# PB_LAN9500.net
KiCad netlist of a schematic drawn in EAGLE
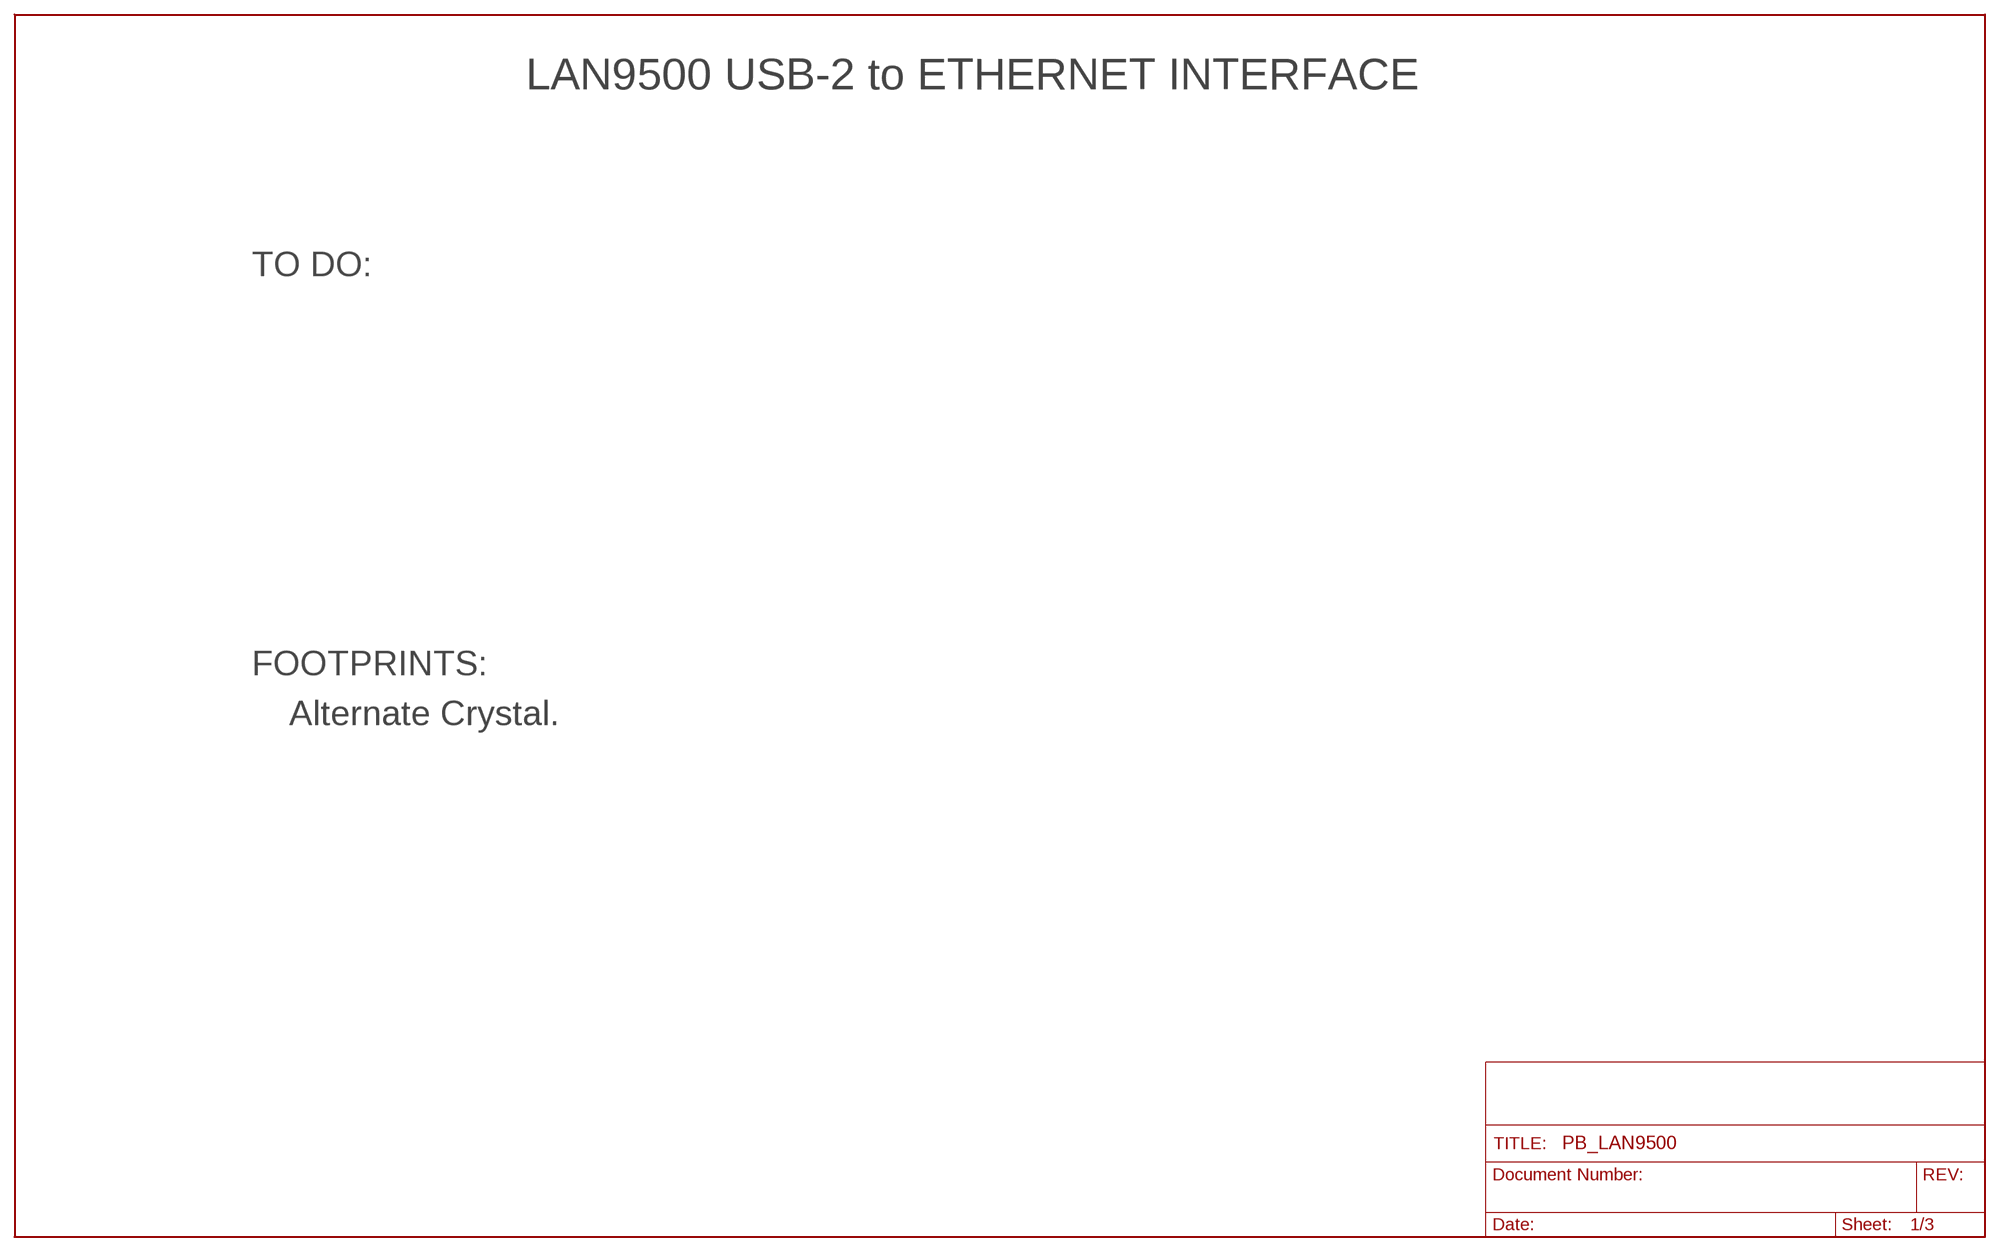
[diagram p0: schematic, sheet 1]
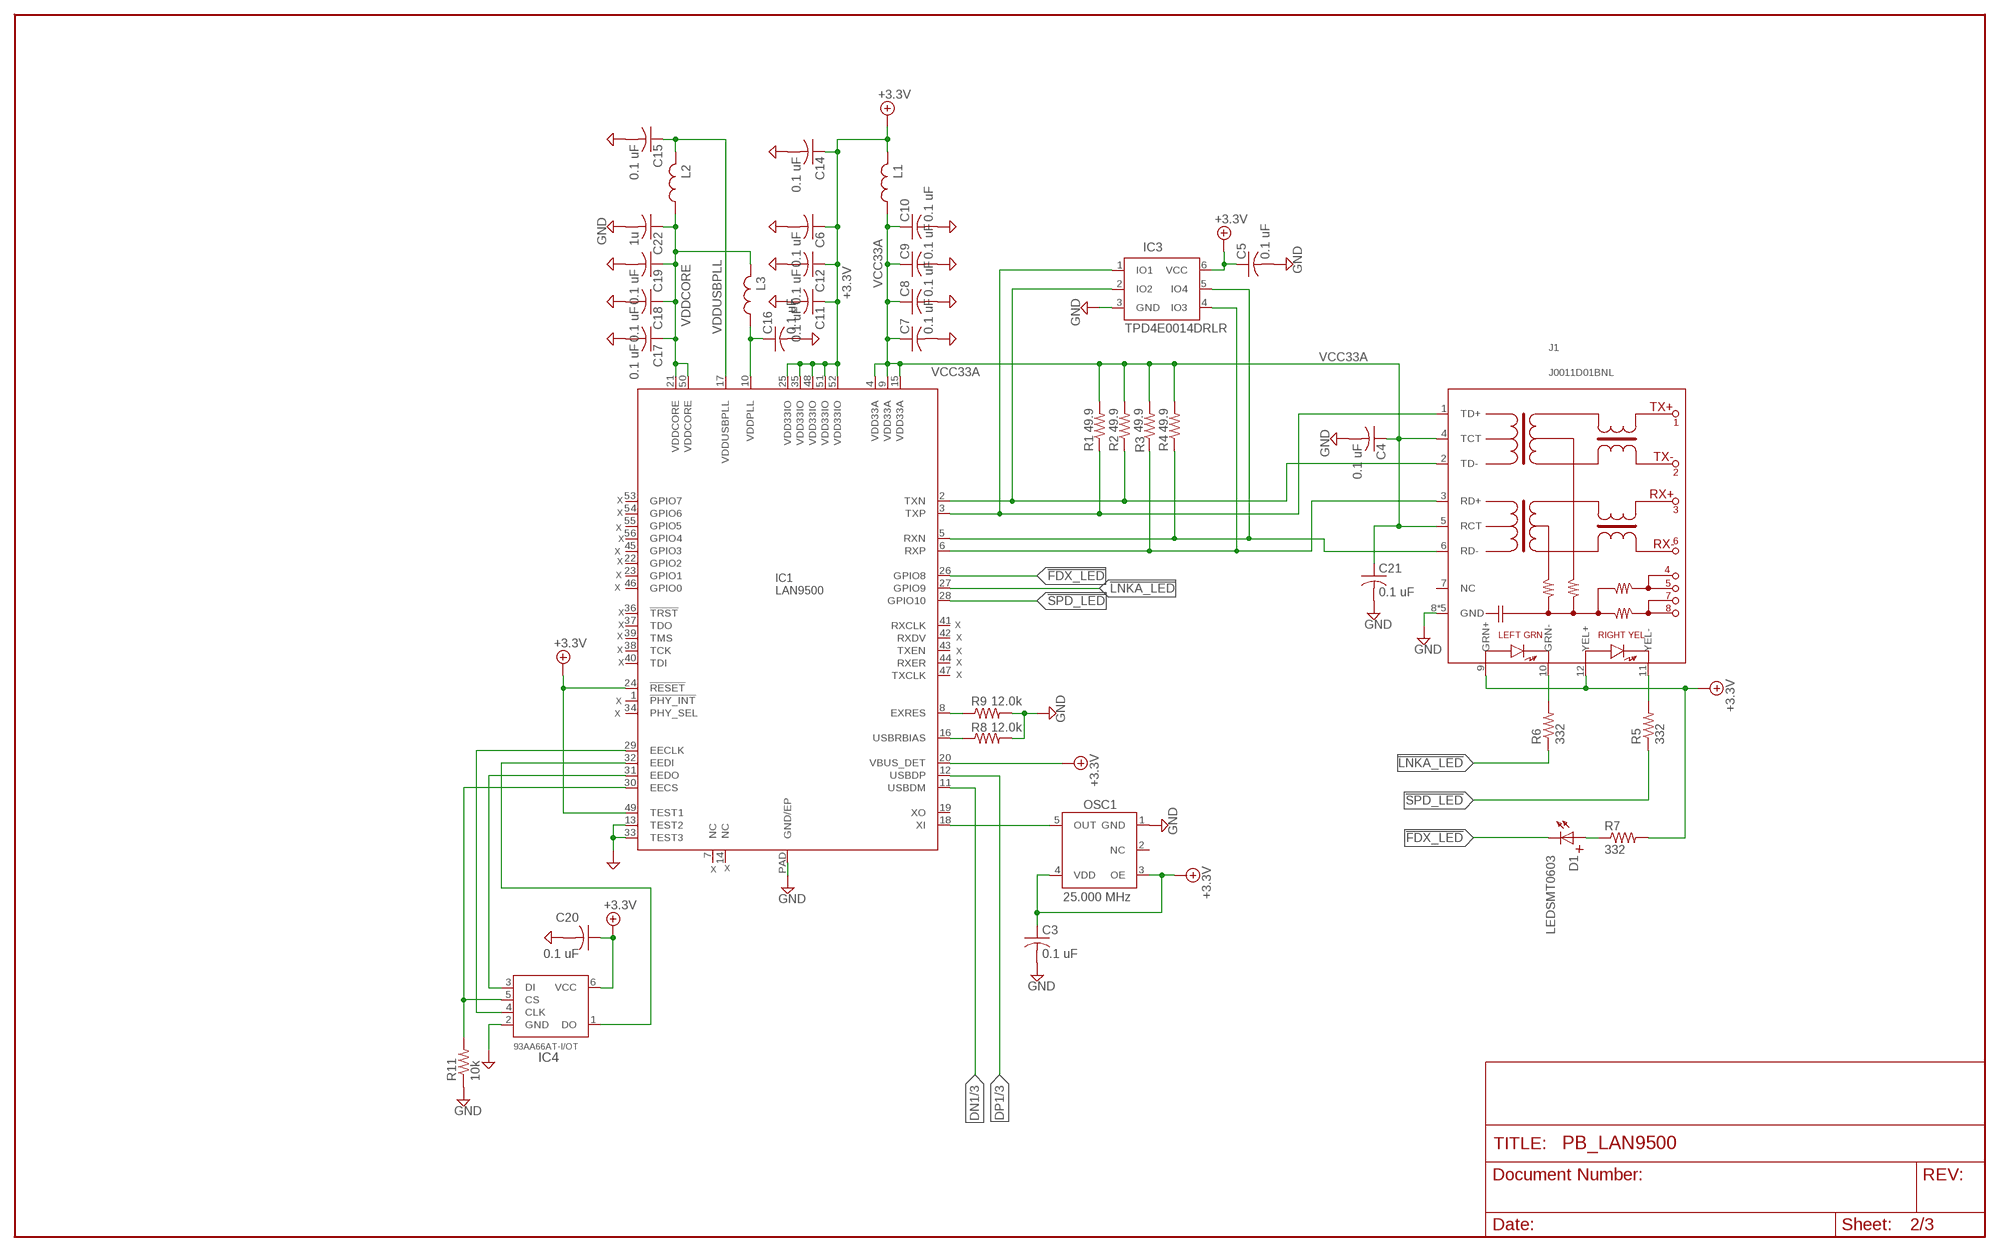
[diagram p1: schematic, sheet 2]
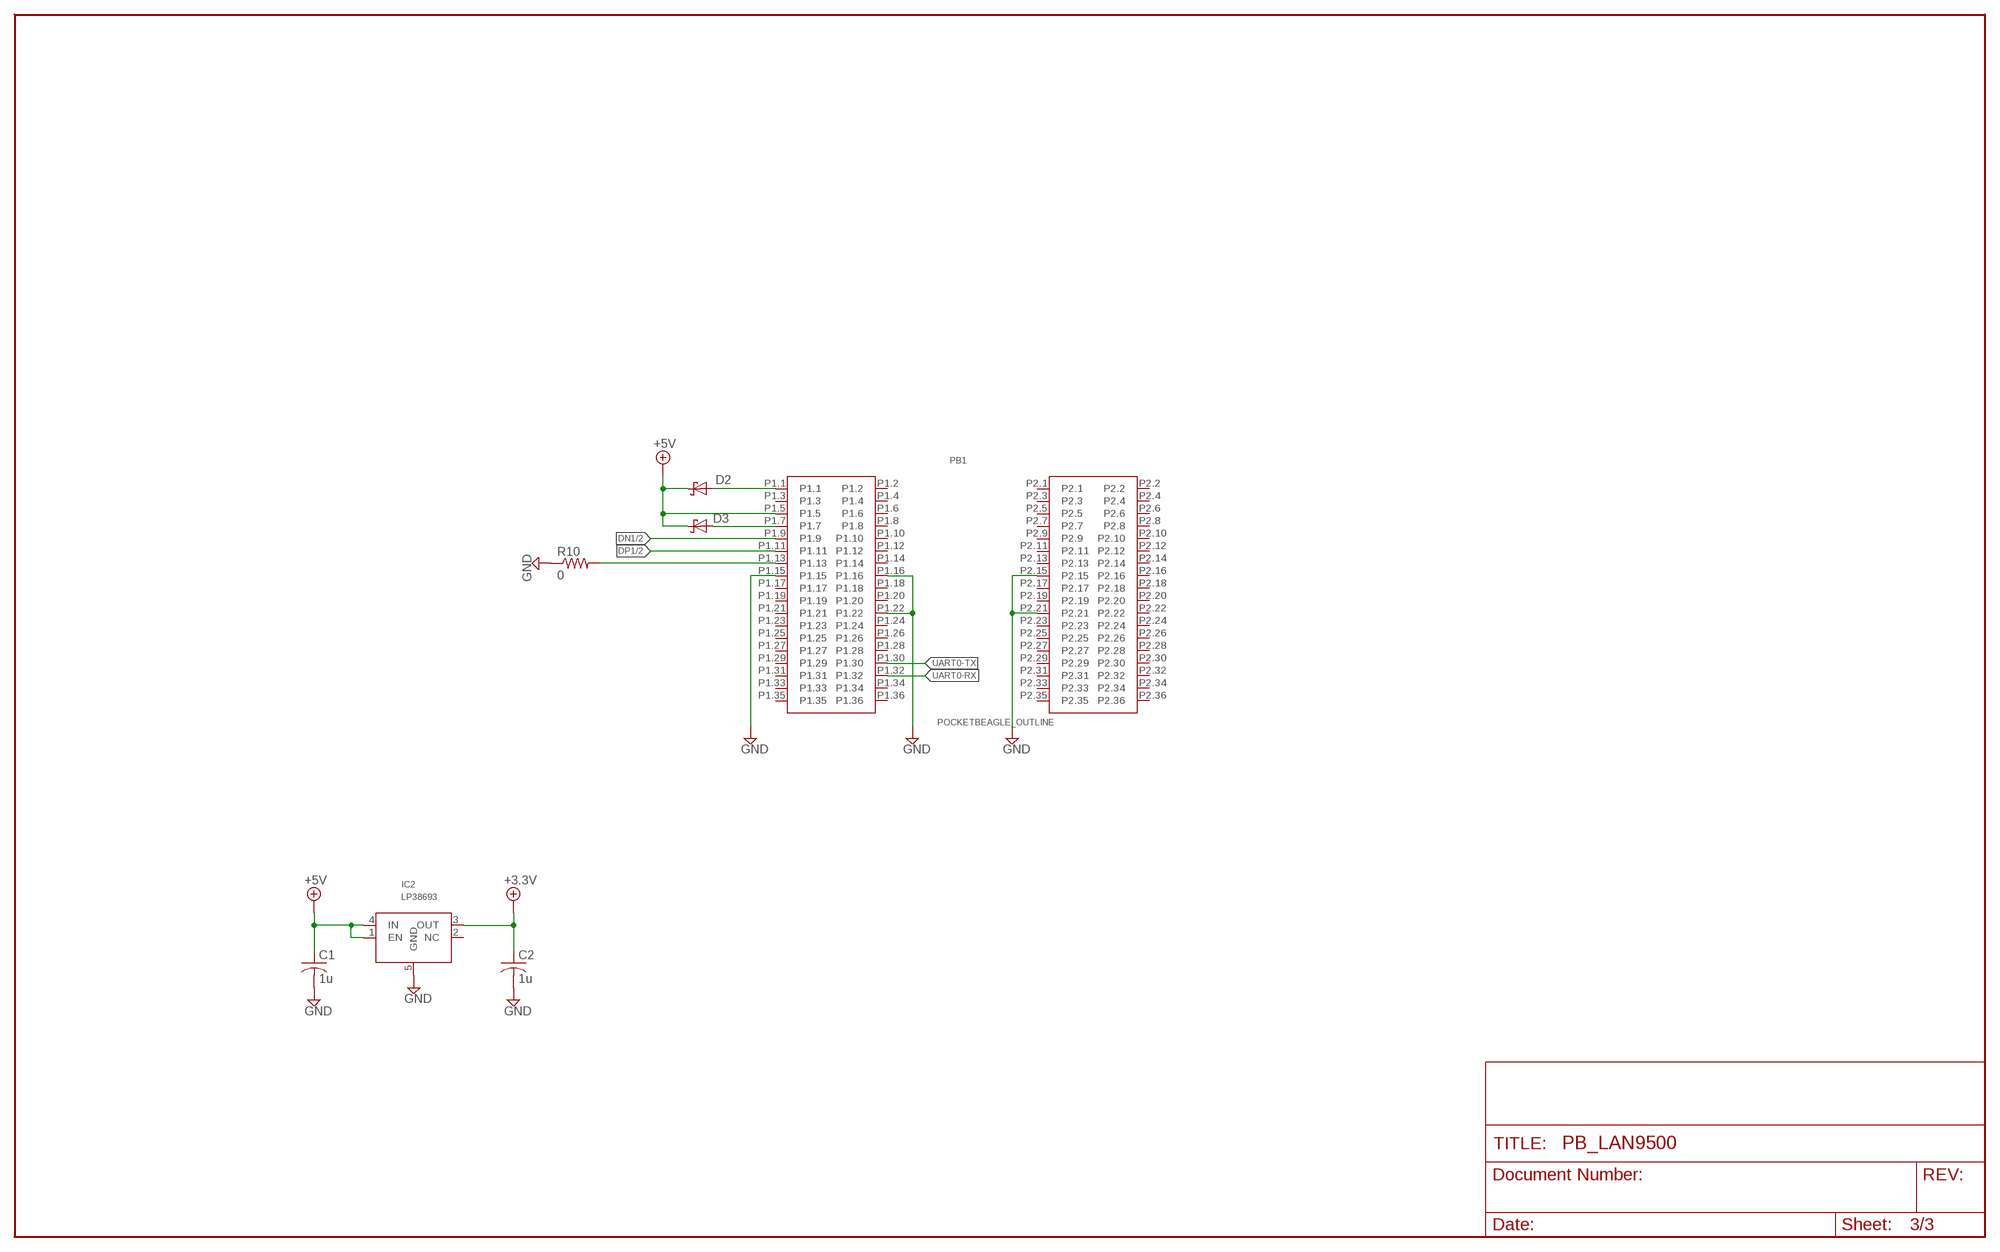
[diagram p2: schematic, sheet 3]

(export (version "E")
  (design (tool "Eeschema 10.0.6"))
  (components
    (comp (ref "C3")
      (value "0.1 uF")
      (footprint "eagle-import:C0402")
      (libsource (lib "eagle-import") (part "C-USC0402"))
    )
    (comp (ref "C4")
      (value "0.1 uF")
      (footprint "eagle-import:C0402")
      (libsource (lib "eagle-import") (part "C-USC0402"))
    )
    (comp (ref "C5")
      (value "0.1 uF")
      (footprint "eagle-import:C0402")
      (libsource (lib "eagle-import") (part "C-USC0402"))
    )
    (comp (ref "C6")
      (value "0.1 uF")
      (footprint "eagle-import:C0402")
      (libsource (lib "eagle-import") (part "C-USC0402"))
    )
    (comp (ref "C7")
      (value "0.1 uF")
      (footprint "eagle-import:C0402")
      (libsource (lib "eagle-import") (part "C-USC0402"))
    )
    (comp (ref "C8")
      (value "0.1 uF")
      (footprint "eagle-import:C0402")
      (libsource (lib "eagle-import") (part "C-USC0402"))
    )
    (comp (ref "C9")
      (value "0.1 uF")
      (footprint "eagle-import:C0402")
      (libsource (lib "eagle-import") (part "C-USC0402"))
    )
    (comp (ref "C10")
      (value "0.1 uF")
      (footprint "eagle-import:C0402")
      (libsource (lib "eagle-import") (part "C-USC0402"))
    )
    (comp (ref "C11")
      (value "0.1 uF")
      (footprint "eagle-import:C0402")
      (libsource (lib "eagle-import") (part "C-USC0402"))
    )
    (comp (ref "C12")
      (value "0.1 uF")
      (footprint "eagle-import:C0402")
      (libsource (lib "eagle-import") (part "C-USC0402"))
    )
    (comp (ref "C14")
      (value "0.1 uF")
      (footprint "eagle-import:C0402")
      (libsource (lib "eagle-import") (part "C-USC0402"))
    )
    (comp (ref "C15")
      (value "0.1 uF")
      (footprint "eagle-import:C0402")
      (libsource (lib "eagle-import") (part "C-USC0402"))
    )
    (comp (ref "C16")
      (value "0.1 uF")
      (footprint "eagle-import:C0402")
      (libsource (lib "eagle-import") (part "C-USC0402"))
    )
    (comp (ref "C17")
      (value "0.1 uF")
      (footprint "eagle-import:C0402")
      (libsource (lib "eagle-import") (part "C-USC0402"))
    )
    (comp (ref "C18")
      (value "0.1 uF")
      (footprint "eagle-import:C0402")
      (libsource (lib "eagle-import") (part "C-USC0402"))
    )
    (comp (ref "C19")
      (value "0.1 uF")
      (footprint "eagle-import:C0402")
      (libsource (lib "eagle-import") (part "C-USC0402"))
    )
    (comp (ref "C20")
      (value "0.1 uF")
      (footprint "eagle-import:C0402")
      (libsource (lib "eagle-import") (part "C-USC0402"))
    )
    (comp (ref "C21")
      (value "0.1 uF")
      (footprint "eagle-import:C0402")
      (libsource (lib "eagle-import") (part "C-USC0402"))
    )
    (comp (ref "C22")
      (value "1u")
      (footprint "eagle-import:C0805")
      (libsource (lib "eagle-import") (part "C-USC0805"))
    )
    (comp (ref "D1")
      (value "LEDSMT0603")
      (footprint "eagle-import:LED0603")
      (libsource (lib "eagle-import") (part "LEDSMT0603"))
    )
    (comp (ref "IC1")
      (value "LAN9500")
      (footprint "eagle-import:QFN56")
      (libsource (lib "eagle-import") (part "LAN9500"))
    )
    (comp (ref "IC3")
      (value "TPD4E0014DRLR")
      (footprint "eagle-import:SOT-553-6")
      (libsource (lib "eagle-import") (part "TPD4E001DRLR4"))
    )
    (comp (ref "IC4")
      (value "93AA66AT-I/OT")
      (footprint "eagle-import:SOT23-6")
      (libsource (lib "eagle-import") (part "93AA66AT-I/OT"))
    )
    (comp (ref "J1")
      (value "J0011D01BNL")
      (footprint "eagle-import:J0011D01BNL")
      (libsource (lib "eagle-import") (part "J0011D01BNL"))
    )
    (comp (ref "L1")
      (value "L0603AS")
      (footprint "eagle-import:L0603AS")
      (libsource (lib "eagle-import") (part "L0603AS"))
    )
    (comp (ref "L2")
      (value "L0603AS")
      (footprint "eagle-import:L0603AS")
      (libsource (lib "eagle-import") (part "L0603AS"))
    )
    (comp (ref "L3")
      (value "L0603AS")
      (footprint "eagle-import:L0603AS")
      (libsource (lib "eagle-import") (part "L0603AS"))
    )
    (comp (ref "OSC1")
      (value "25.000 MHz")
      (footprint "eagle-import:SOT23-5")
      (libsource (lib "eagle-import") (part "SIT2024B"))
    )
    (comp (ref "R1")
      (value "49.9")
      (footprint "eagle-import:R0603")
      (libsource (lib "eagle-import") (part "R-US_R0603"))
    )
    (comp (ref "R2")
      (value "49.9")
      (footprint "eagle-import:R0603")
      (libsource (lib "eagle-import") (part "R-US_R0603"))
    )
    (comp (ref "R3")
      (value "49.9")
      (footprint "eagle-import:R0603")
      (libsource (lib "eagle-import") (part "R-US_R0603"))
    )
    (comp (ref "R4")
      (value "49.9")
      (footprint "eagle-import:R0603")
      (libsource (lib "eagle-import") (part "R-US_R0603"))
    )
    (comp (ref "R5")
      (value "332")
      (footprint "eagle-import:R0603")
      (libsource (lib "eagle-import") (part "R-US_R0603"))
    )
    (comp (ref "R6")
      (value "332")
      (footprint "eagle-import:R0603")
      (libsource (lib "eagle-import") (part "R-US_R0603"))
    )
    (comp (ref "R7")
      (value "332")
      (footprint "eagle-import:R0603")
      (libsource (lib "eagle-import") (part "R-US_R0603"))
    )
    (comp (ref "R8")
      (value "12.0k")
      (footprint "eagle-import:R0603")
      (libsource (lib "eagle-import") (part "R-US_R0603"))
    )
    (comp (ref "R9")
      (value "12.0k")
      (footprint "eagle-import:R0603")
      (libsource (lib "eagle-import") (part "R-US_R0603"))
    )
    (comp (ref "R11")
      (value "10k")
      (footprint "eagle-import:R0603")
      (libsource (lib "eagle-import") (part "R-US_R0603"))
    )
    (comp (ref "C1")
      (value "1u")
      (footprint "eagle-import:C0805")
      (libsource (lib "eagle-import") (part "C-USC0805"))
    )
    (comp (ref "C2")
      (value "1u")
      (footprint "eagle-import:C0805")
      (libsource (lib "eagle-import") (part "C-USC0805"))
    )
    (comp (ref "D2")
      (value "MBRAF1540")
      (footprint "eagle-import:SMA-FL")
      (libsource (lib "eagle-import") (part "MBRAF1540"))
    )
    (comp (ref "D3")
      (value "MBRAF1540")
      (footprint "eagle-import:SMA-FL")
      (libsource (lib "eagle-import") (part "MBRAF1540"))
    )
    (comp (ref "IC2")
      (value "LP38693")
      (footprint "eagle-import:SOT-223-4")
      (libsource (lib "eagle-import") (part "LP38693"))
    )
    (comp (ref "PB1")
      (value "POCKETBEAGLE_OUTLINE")
      (footprint "eagle-import:PB_OUTLINE")
      (libsource (lib "eagle-import") (part "POCKETBEAGLE_OUTLINE"))
    )
    (comp (ref "R10")
      (value "0")
      (footprint "eagle-import:R0603")
      (libsource (lib "eagle-import") (part "R-US_R0603"))
    )
  )
  (nets
    (net (code "1") (name "+3.3V") (class "Default")
      (node (ref "C11") (pin "1") (pinfunction "1_1") (pintype "passive"))
      (node (ref "C12") (pin "1") (pinfunction "1_1") (pintype "passive"))
      (node (ref "C14") (pin "1") (pinfunction "1_1") (pintype "passive"))
      (node (ref "C2") (pin "1") (pinfunction "1_1") (pintype "passive"))
      (node (ref "C20") (pin "1") (pinfunction "1_1") (pintype "passive"))
      (node (ref "C3") (pin "1") (pinfunction "1_1") (pintype "passive"))
      (node (ref "C5") (pin "1") (pinfunction "1_1") (pintype "passive"))
      (node (ref "C6") (pin "1") (pinfunction "1_1") (pintype "passive"))
      (node (ref "IC1") (pin "20") (pinfunction "VBUS_DET_20") (pintype "bidirectional"))
      (node (ref "IC1") (pin "24") (pinfunction "~{RESET}_24") (pintype "bidirectional"))
      (node (ref "IC1") (pin "25") (pinfunction "VDD33IO_25") (pintype "bidirectional"))
      (node (ref "IC1") (pin "35") (pinfunction "VDD33IO_35") (pintype "bidirectional"))
      (node (ref "IC1") (pin "48") (pinfunction "VDD33IO_48") (pintype "bidirectional"))
      (node (ref "IC1") (pin "49") (pinfunction "TEST1_49") (pintype "bidirectional"))
      (node (ref "IC1") (pin "51") (pinfunction "VDD33IO_51") (pintype "bidirectional"))
      (node (ref "IC1") (pin "52") (pinfunction "VDD33IO_52") (pintype "bidirectional"))
      (node (ref "IC2") (pin "3") (pinfunction "OUT_3") (pintype "bidirectional"))
      (node (ref "IC3") (pin "6") (pinfunction "VCC_6") (pintype "power_in"))
      (node (ref "IC4") (pin "6") (pinfunction "VCC_6") (pintype "bidirectional"))
      (node (ref "J1") (pin "12") (pinfunction "YEL+_12") (pintype "bidirectional"))
      (node (ref "J1") (pin "9") (pinfunction "GRN+_9") (pintype "bidirectional"))
      (node (ref "L1") (pin "2") (pinfunction "2_2") (pintype "passive"))
      (node (ref "OSC1") (pin "3") (pinfunction "OE_3") (pintype "bidirectional"))
      (node (ref "OSC1") (pin "4") (pinfunction "VDD_4") (pintype "bidirectional"))
      (node (ref "R7") (pin "2") (pinfunction "2_2") (pintype "passive"))
    )
    (net (code "2") (name "+5V") (class "Default")
      (node (ref "C1") (pin "1") (pinfunction "1_1") (pintype "passive"))
      (node (ref "D2") (pin "C") (pinfunction "C_C") (pintype "passive"))
      (node (ref "D3") (pin "C") (pinfunction "C_C") (pintype "passive"))
      (node (ref "IC2") (pin "1") (pinfunction "EN_1") (pintype "input"))
      (node (ref "IC2") (pin "4") (pinfunction "IN_4") (pintype "bidirectional"))
      (node (ref "PB1") (pin "P1.5") (pinfunction "P1.5_P1.5") (pintype "bidirectional"))
    )
    (net (code "3") (name "DN1") (class "Default")
      (node (ref "IC1") (pin "11") (pinfunction "USBDM_11") (pintype "bidirectional"))
      (node (ref "PB1") (pin "P1.9") (pinfunction "P1.9_P1.9") (pintype "bidirectional"))
    )
    (net (code "4") (name "DP1") (class "Default")
      (node (ref "IC1") (pin "12") (pinfunction "USBDP_12") (pintype "bidirectional"))
      (node (ref "PB1") (pin "P1.11") (pinfunction "P1.11_P1.11") (pintype "bidirectional"))
    )
    (net (code "5") (name "GND") (class "Default")
      (node (ref "C1") (pin "2") (pinfunction "2_2") (pintype "passive"))
      (node (ref "C10") (pin "2") (pinfunction "2_2") (pintype "passive"))
      (node (ref "C11") (pin "2") (pinfunction "2_2") (pintype "passive"))
      (node (ref "C12") (pin "2") (pinfunction "2_2") (pintype "passive"))
      (node (ref "C14") (pin "2") (pinfunction "2_2") (pintype "passive"))
      (node (ref "C15") (pin "2") (pinfunction "2_2") (pintype "passive"))
      (node (ref "C16") (pin "2") (pinfunction "2_2") (pintype "passive"))
      (node (ref "C17") (pin "2") (pinfunction "2_2") (pintype "passive"))
      (node (ref "C18") (pin "2") (pinfunction "2_2") (pintype "passive"))
      (node (ref "C19") (pin "2") (pinfunction "2_2") (pintype "passive"))
      (node (ref "C2") (pin "2") (pinfunction "2_2") (pintype "passive"))
      (node (ref "C20") (pin "2") (pinfunction "2_2") (pintype "passive"))
      (node (ref "C21") (pin "2") (pinfunction "2_2") (pintype "passive"))
      (node (ref "C22") (pin "2") (pinfunction "2_2") (pintype "passive"))
      (node (ref "C3") (pin "2") (pinfunction "2_2") (pintype "passive"))
      (node (ref "C4") (pin "2") (pinfunction "2_2") (pintype "passive"))
      (node (ref "C5") (pin "2") (pinfunction "2_2") (pintype "passive"))
      (node (ref "C6") (pin "2") (pinfunction "2_2") (pintype "passive"))
      (node (ref "C7") (pin "2") (pinfunction "2_2") (pintype "passive"))
      (node (ref "C8") (pin "2") (pinfunction "2_2") (pintype "passive"))
      (node (ref "C9") (pin "2") (pinfunction "2_2") (pintype "passive"))
      (node (ref "IC1") (pin "13") (pinfunction "TEST2_13") (pintype "bidirectional"))
      (node (ref "IC1") (pin "33") (pinfunction "TEST3_33") (pintype "bidirectional"))
      (node (ref "IC1") (pin "PAD") (pinfunction "GND/EP_PAD") (pintype "bidirectional"))
      (node (ref "IC2") (pin "5") (pinfunction "GND_5") (pintype "power_in"))
      (node (ref "IC3") (pin "3") (pinfunction "GND_3") (pintype "power_in"))
      (node (ref "IC4") (pin "2") (pinfunction "GND_2") (pintype "bidirectional"))
      (node (ref "J1") (pin "8") (pinfunction "GND_8") (pintype "bidirectional"))
      (node (ref "J1") (pin "GND1") (pinfunction "GND_GND1") (pintype "bidirectional"))
      (node (ref "J1") (pin "GND2") (pinfunction "GND_GND2") (pintype "bidirectional"))
      (node (ref "J1") (pin "GND3") (pinfunction "GND_GND3") (pintype "bidirectional"))
      (node (ref "J1") (pin "GND4") (pinfunction "GND_GND4") (pintype "bidirectional"))
      (node (ref "OSC1") (pin "1") (pinfunction "GND_1") (pintype "bidirectional"))
      (node (ref "PB1") (pin "P1.15") (pinfunction "P1.15_P1.15") (pintype "bidirectional"))
      (node (ref "PB1") (pin "P1.16") (pinfunction "P1.16_P1.16") (pintype "bidirectional"))
      (node (ref "PB1") (pin "P1.22") (pinfunction "P1.22_P1.22") (pintype "bidirectional"))
      (node (ref "PB1") (pin "P2.15") (pinfunction "P2.15_P2.15") (pintype "bidirectional"))
      (node (ref "PB1") (pin "P2.21") (pinfunction "P2.21_P2.21") (pintype "bidirectional"))
      (node (ref "R10") (pin "1") (pinfunction "1_1") (pintype "passive"))
      (node (ref "R11") (pin "1") (pinfunction "1_1") (pintype "passive"))
      (node (ref "R8") (pin "2") (pinfunction "2_2") (pintype "passive"))
      (node (ref "R9") (pin "2") (pinfunction "2_2") (pintype "passive"))
    )
    (net (code "6") (name "Net-(D1-A)") (class "Default")
      (node (ref "D1") (pin "P$1") (pinfunction "A_P$1") (pintype "passive"))
      (node (ref "R7") (pin "1") (pinfunction "1_1") (pintype "passive"))
    )
    (net (code "7") (name "Net-(D2-PadA)") (class "Default")
      (node (ref "D2") (pin "A") (pinfunction "A_A") (pintype "passive"))
      (node (ref "PB1") (pin "P1.1") (pinfunction "P1.1_P1.1") (pintype "bidirectional"))
    )
    (net (code "8") (name "Net-(D3-PadA)") (class "Default")
      (node (ref "D3") (pin "A") (pinfunction "A_A") (pintype "passive"))
      (node (ref "PB1") (pin "P1.7") (pinfunction "P1.7_P1.7") (pintype "bidirectional"))
    )
    (net (code "9") (name "Net-(IC1-EECLK)") (class "Default")
      (node (ref "IC1") (pin "29") (pinfunction "EECLK_29") (pintype "bidirectional"))
      (node (ref "IC4") (pin "4") (pinfunction "CLK_4") (pintype "bidirectional"))
    )
    (net (code "10") (name "Net-(IC1-EECS)") (class "Default")
      (node (ref "IC1") (pin "30") (pinfunction "EECS_30") (pintype "bidirectional"))
      (node (ref "IC4") (pin "5") (pinfunction "CS_5") (pintype "bidirectional"))
      (node (ref "R11") (pin "2") (pinfunction "2_2") (pintype "passive"))
    )
    (net (code "11") (name "Net-(IC1-EEDI)") (class "Default")
      (node (ref "IC1") (pin "32") (pinfunction "EEDI_32") (pintype "bidirectional"))
      (node (ref "IC4") (pin "1") (pinfunction "DO_1") (pintype "bidirectional"))
    )
    (net (code "12") (name "Net-(IC1-EEDO)") (class "Default")
      (node (ref "IC1") (pin "31") (pinfunction "EEDO_31") (pintype "bidirectional"))
      (node (ref "IC4") (pin "3") (pinfunction "DI_3") (pintype "bidirectional"))
    )
    (net (code "13") (name "Net-(IC1-EXRES)") (class "Default")
      (node (ref "IC1") (pin "8") (pinfunction "EXRES_8") (pintype "bidirectional"))
      (node (ref "R9") (pin "1") (pinfunction "1_1") (pintype "passive"))
    )
    (net (code "14") (name "Net-(IC1-RXN)") (class "Default")
      (node (ref "IC1") (pin "5") (pinfunction "RXN_5") (pintype "bidirectional"))
      (node (ref "IC3") (pin "5") (pinfunction "IO4_5") (pintype "passive"))
      (node (ref "J1") (pin "6") (pinfunction "RD-_6") (pintype "bidirectional"))
      (node (ref "R4") (pin "1") (pinfunction "1_1") (pintype "passive"))
    )
    (net (code "15") (name "Net-(IC1-RXP)") (class "Default")
      (node (ref "IC1") (pin "6") (pinfunction "RXP_6") (pintype "bidirectional"))
      (node (ref "IC3") (pin "4") (pinfunction "IO3_4") (pintype "passive"))
      (node (ref "J1") (pin "3") (pinfunction "RD+_3") (pintype "bidirectional"))
      (node (ref "R3") (pin "1") (pinfunction "1_1") (pintype "passive"))
    )
    (net (code "16") (name "Net-(IC1-TXN)") (class "Default")
      (node (ref "IC1") (pin "2") (pinfunction "TXN_2") (pintype "bidirectional"))
      (node (ref "IC3") (pin "2") (pinfunction "IO2_2") (pintype "passive"))
      (node (ref "J1") (pin "2") (pinfunction "TD-_2") (pintype "bidirectional"))
      (node (ref "R2") (pin "1") (pinfunction "1_1") (pintype "passive"))
    )
    (net (code "17") (name "Net-(IC1-TXP)") (class "Default")
      (node (ref "IC1") (pin "3") (pinfunction "TXP_3") (pintype "bidirectional"))
      (node (ref "IC3") (pin "1") (pinfunction "IO1_1") (pintype "passive"))
      (node (ref "J1") (pin "1") (pinfunction "TD+_1") (pintype "bidirectional"))
      (node (ref "R1") (pin "1") (pinfunction "1_1") (pintype "passive"))
    )
    (net (code "18") (name "Net-(IC1-USBRBIAS)") (class "Default")
      (node (ref "IC1") (pin "16") (pinfunction "USBRBIAS_16") (pintype "bidirectional"))
      (node (ref "R8") (pin "1") (pinfunction "1_1") (pintype "passive"))
    )
    (net (code "19") (name "Net-(IC1-VDDPLL)") (class "Default")
      (node (ref "C16") (pin "1") (pinfunction "1_1") (pintype "passive"))
      (node (ref "IC1") (pin "10") (pinfunction "VDDPLL_10") (pintype "bidirectional"))
      (node (ref "L3") (pin "1") (pinfunction "1_1") (pintype "passive"))
    )
    (net (code "20") (name "Net-(IC1-XI)") (class "Default")
      (node (ref "IC1") (pin "18") (pinfunction "XI_18") (pintype "bidirectional"))
      (node (ref "OSC1") (pin "5") (pinfunction "OUT_5") (pintype "bidirectional"))
    )
    (net (code "21") (name "Net-(J1-GRN-)") (class "Default")
      (node (ref "J1") (pin "10") (pinfunction "GRN-_10") (pintype "bidirectional"))
      (node (ref "R6") (pin "2") (pinfunction "2_2") (pintype "passive"))
    )
    (net (code "22") (name "Net-(J1-YEL-)") (class "Default")
      (node (ref "J1") (pin "11") (pinfunction "YEL-_11") (pintype "bidirectional"))
      (node (ref "R5") (pin "2") (pinfunction "2_2") (pintype "passive"))
    )
    (net (code "23") (name "Net-(PB1-PadP1.13)") (class "Default")
      (node (ref "PB1") (pin "P1.13") (pinfunction "P1.13_P1.13") (pintype "bidirectional"))
      (node (ref "R10") (pin "2") (pinfunction "2_2") (pintype "passive"))
    )
    (net (code "24") (name "UART0-RX") (class "Default")
      (node (ref "PB1") (pin "P1.32") (pinfunction "P1.32_P1.32") (pintype "bidirectional"))
    )
    (net (code "25") (name "UART0-TX") (class "Default")
      (node (ref "PB1") (pin "P1.30") (pinfunction "P1.30_P1.30") (pintype "bidirectional"))
    )
    (net (code "26") (name "VCC33A") (class "Default")
      (node (ref "C10") (pin "1") (pinfunction "1_1") (pintype "passive"))
      (node (ref "C21") (pin "1") (pinfunction "1_1") (pintype "passive"))
      (node (ref "C4") (pin "1") (pinfunction "1_1") (pintype "passive"))
      (node (ref "C7") (pin "1") (pinfunction "1_1") (pintype "passive"))
      (node (ref "C8") (pin "1") (pinfunction "1_1") (pintype "passive"))
      (node (ref "C9") (pin "1") (pinfunction "1_1") (pintype "passive"))
      (node (ref "IC1") (pin "15") (pinfunction "VDD33A_15") (pintype "bidirectional"))
      (node (ref "IC1") (pin "4") (pinfunction "VDD33A_4") (pintype "bidirectional"))
      (node (ref "IC1") (pin "9") (pinfunction "VDD33A_9") (pintype "bidirectional"))
      (node (ref "J1") (pin "4") (pinfunction "TCT_4") (pintype "bidirectional"))
      (node (ref "J1") (pin "5") (pinfunction "RCT_5") (pintype "bidirectional"))
      (node (ref "L1") (pin "1") (pinfunction "1_1") (pintype "passive"))
      (node (ref "R1") (pin "2") (pinfunction "2_2") (pintype "passive"))
      (node (ref "R2") (pin "2") (pinfunction "2_2") (pintype "passive"))
      (node (ref "R3") (pin "2") (pinfunction "2_2") (pintype "passive"))
      (node (ref "R4") (pin "2") (pinfunction "2_2") (pintype "passive"))
    )
    (net (code "27") (name "VDDCORE") (class "Default")
      (node (ref "C17") (pin "1") (pinfunction "1_1") (pintype "passive"))
      (node (ref "C18") (pin "1") (pinfunction "1_1") (pintype "passive"))
      (node (ref "C19") (pin "1") (pinfunction "1_1") (pintype "passive"))
      (node (ref "C22") (pin "1") (pinfunction "1_1") (pintype "passive"))
      (node (ref "IC1") (pin "21") (pinfunction "VDDCORE_21") (pintype "bidirectional"))
      (node (ref "IC1") (pin "50") (pinfunction "VDDCORE_50") (pintype "bidirectional"))
      (node (ref "L2") (pin "1") (pinfunction "1_1") (pintype "passive"))
      (node (ref "L3") (pin "2") (pinfunction "2_2") (pintype "passive"))
    )
    (net (code "28") (name "VDDUSBPLL") (class "Default")
      (node (ref "C15") (pin "1") (pinfunction "1_1") (pintype "passive"))
      (node (ref "IC1") (pin "17") (pinfunction "VDDUSBPLL_17") (pintype "bidirectional"))
      (node (ref "L2") (pin "2") (pinfunction "2_2") (pintype "passive"))
    )
    (net (code "29") (name "unconnected-(IC1-GPIO0-Pad46)") (class "Default")
      (node (ref "IC1") (pin "46") (pinfunction "GPIO0_46") (pintype "bidirectional"))
    )
    (net (code "30") (name "unconnected-(IC1-GPIO1-Pad23)") (class "Default")
      (node (ref "IC1") (pin "23") (pinfunction "GPIO1_23") (pintype "bidirectional"))
    )
    (net (code "31") (name "unconnected-(IC1-GPIO2-Pad22)") (class "Default")
      (node (ref "IC1") (pin "22") (pinfunction "GPIO2_22") (pintype "bidirectional"))
    )
    (net (code "32") (name "unconnected-(IC1-GPIO3-Pad45)") (class "Default")
      (node (ref "IC1") (pin "45") (pinfunction "GPIO3_45") (pintype "bidirectional"))
    )
    (net (code "33") (name "unconnected-(IC1-GPIO4-Pad56)") (class "Default")
      (node (ref "IC1") (pin "56") (pinfunction "GPIO4_56") (pintype "bidirectional"))
    )
    (net (code "34") (name "unconnected-(IC1-GPIO5-Pad55)") (class "Default")
      (node (ref "IC1") (pin "55") (pinfunction "GPIO5_55") (pintype "bidirectional"))
    )
    (net (code "35") (name "unconnected-(IC1-GPIO6-Pad54)") (class "Default")
      (node (ref "IC1") (pin "54") (pinfunction "GPIO6_54") (pintype "bidirectional"))
    )
    (net (code "36") (name "unconnected-(IC1-GPIO7-Pad53)") (class "Default")
      (node (ref "IC1") (pin "53") (pinfunction "GPIO7_53") (pintype "bidirectional"))
    )
    (net (code "37") (name "unconnected-(IC1-NC-Pad7)") (class "Default")
      (node (ref "IC1") (pin "7") (pinfunction "NC_7") (pintype "bidirectional"))
    )
    (net (code "38") (name "unconnected-(IC1-NC-Pad14)") (class "Default")
      (node (ref "IC1") (pin "14") (pinfunction "NC_14") (pintype "bidirectional"))
    )
    (net (code "39") (name "unconnected-(IC1-PHY_SEL-Pad34)") (class "Default")
      (node (ref "IC1") (pin "34") (pinfunction "PHY_SEL_34") (pintype "bidirectional"))
    )
    (net (code "40") (name "unconnected-(IC1-RXCLK-Pad41)") (class "Default")
      (node (ref "IC1") (pin "41") (pinfunction "RXCLK_41") (pintype "bidirectional"))
    )
    (net (code "41") (name "unconnected-(IC1-RXDV-Pad42)") (class "Default")
      (node (ref "IC1") (pin "42") (pinfunction "RXDV_42") (pintype "bidirectional"))
    )
    (net (code "42") (name "unconnected-(IC1-RXER-Pad44)") (class "Default")
      (node (ref "IC1") (pin "44") (pinfunction "RXER_44") (pintype "bidirectional"))
    )
    (net (code "43") (name "unconnected-(IC1-TCK-Pad38)") (class "Default")
      (node (ref "IC1") (pin "38") (pinfunction "TCK_38") (pintype "bidirectional"))
    )
    (net (code "44") (name "unconnected-(IC1-TDI-Pad40)") (class "Default")
      (node (ref "IC1") (pin "40") (pinfunction "TDI_40") (pintype "bidirectional"))
    )
    (net (code "45") (name "unconnected-(IC1-TDO-Pad37)") (class "Default")
      (node (ref "IC1") (pin "37") (pinfunction "TDO_37") (pintype "bidirectional"))
    )
    (net (code "46") (name "unconnected-(IC1-TMS-Pad39)") (class "Default")
      (node (ref "IC1") (pin "39") (pinfunction "TMS_39") (pintype "bidirectional"))
    )
    (net (code "47") (name "unconnected-(IC1-TXCLK-Pad47)") (class "Default")
      (node (ref "IC1") (pin "47") (pinfunction "TXCLK_47") (pintype "bidirectional"))
    )
    (net (code "48") (name "unconnected-(IC1-TXEN-Pad43)") (class "Default")
      (node (ref "IC1") (pin "43") (pinfunction "TXEN_43") (pintype "bidirectional"))
    )
    (net (code "49") (name "unconnected-(IC1-XO-Pad19)") (class "Default")
      (node (ref "IC1") (pin "19") (pinfunction "XO_19") (pintype "bidirectional"))
    )
    (net (code "50") (name "unconnected-(IC1-~{PHY_INT}-Pad1)") (class "Default")
      (node (ref "IC1") (pin "1") (pinfunction "~{PHY_INT}_1") (pintype "bidirectional"))
    )
    (net (code "51") (name "unconnected-(IC1-~{TRST}-Pad36)") (class "Default")
      (node (ref "IC1") (pin "36") (pinfunction "~{TRST}_36") (pintype "bidirectional"))
    )
    (net (code "52") (name "unconnected-(IC2-NC-Pad2)") (class "Default")
      (node (ref "IC2") (pin "2") (pinfunction "NC_2") (pintype "no_connect"))
    )
    (net (code "53") (name "unconnected-(J1-NC-Pad7)") (class "Default")
      (node (ref "J1") (pin "7") (pinfunction "NC_7") (pintype "bidirectional"))
    )
    (net (code "54") (name "unconnected-(OSC1-NC-Pad2)") (class "Default")
      (node (ref "OSC1") (pin "2") (pinfunction "NC_2") (pintype "bidirectional"))
    )
    (net (code "55") (name "unconnected-(PB1-PadP1.2)") (class "Default")
      (node (ref "PB1") (pin "P1.2") (pinfunction "P1.2_P1.2") (pintype "bidirectional"))
    )
    (net (code "56") (name "unconnected-(PB1-PadP1.3)") (class "Default")
      (node (ref "PB1") (pin "P1.3") (pinfunction "P1.3_P1.3") (pintype "bidirectional"))
    )
    (net (code "57") (name "unconnected-(PB1-PadP1.4)") (class "Default")
      (node (ref "PB1") (pin "P1.4") (pinfunction "P1.4_P1.4") (pintype "bidirectional"))
    )
    (net (code "58") (name "unconnected-(PB1-PadP1.6)") (class "Default")
      (node (ref "PB1") (pin "P1.6") (pinfunction "P1.6_P1.6") (pintype "bidirectional"))
    )
    (net (code "59") (name "unconnected-(PB1-PadP1.8)") (class "Default")
      (node (ref "PB1") (pin "P1.8") (pinfunction "P1.8_P1.8") (pintype "bidirectional"))
    )
    (net (code "60") (name "unconnected-(PB1-PadP1.10)") (class "Default")
      (node (ref "PB1") (pin "P1.10") (pinfunction "P1.10_P1.10") (pintype "bidirectional"))
    )
    (net (code "61") (name "unconnected-(PB1-PadP1.12)") (class "Default")
      (node (ref "PB1") (pin "P1.12") (pinfunction "P1.12_P1.12") (pintype "bidirectional"))
    )
    (net (code "62") (name "unconnected-(PB1-PadP1.14)") (class "Default")
      (node (ref "PB1") (pin "P1.14") (pinfunction "P1.14_P1.14") (pintype "bidirectional"))
    )
    (net (code "63") (name "unconnected-(PB1-PadP1.17)") (class "Default")
      (node (ref "PB1") (pin "P1.17") (pinfunction "P1.17_P1.17") (pintype "bidirectional"))
    )
    (net (code "64") (name "unconnected-(PB1-PadP1.18)") (class "Default")
      (node (ref "PB1") (pin "P1.18") (pinfunction "P1.18_P1.18") (pintype "bidirectional"))
    )
    (net (code "65") (name "unconnected-(PB1-PadP1.19)") (class "Default")
      (node (ref "PB1") (pin "P1.19") (pinfunction "P1.19_P1.19") (pintype "bidirectional"))
    )
    (net (code "66") (name "unconnected-(PB1-PadP1.20)") (class "Default")
      (node (ref "PB1") (pin "P1.20") (pinfunction "P1.20_P1.20") (pintype "bidirectional"))
    )
    (net (code "67") (name "unconnected-(PB1-PadP1.21)") (class "Default")
      (node (ref "PB1") (pin "P1.21") (pinfunction "P1.21_P1.21") (pintype "bidirectional"))
    )
    (net (code "68") (name "unconnected-(PB1-PadP1.23)") (class "Default")
      (node (ref "PB1") (pin "P1.23") (pinfunction "P1.23_P1.23") (pintype "bidirectional"))
    )
    (net (code "69") (name "unconnected-(PB1-PadP1.24)") (class "Default")
      (node (ref "PB1") (pin "P1.24") (pinfunction "P1.24_P1.24") (pintype "bidirectional"))
    )
    (net (code "70") (name "unconnected-(PB1-PadP1.25)") (class "Default")
      (node (ref "PB1") (pin "P1.25") (pinfunction "P1.25_P1.25") (pintype "bidirectional"))
    )
    (net (code "71") (name "unconnected-(PB1-PadP1.26)") (class "Default")
      (node (ref "PB1") (pin "P1.26") (pinfunction "P1.26_P1.26") (pintype "bidirectional"))
    )
    (net (code "72") (name "unconnected-(PB1-PadP1.27)") (class "Default")
      (node (ref "PB1") (pin "P1.27") (pinfunction "P1.27_P1.27") (pintype "bidirectional"))
    )
    (net (code "73") (name "unconnected-(PB1-PadP1.28)") (class "Default")
      (node (ref "PB1") (pin "P1.28") (pinfunction "P1.28_P1.28") (pintype "bidirectional"))
    )
    (net (code "74") (name "unconnected-(PB1-PadP1.29)") (class "Default")
      (node (ref "PB1") (pin "P1.29") (pinfunction "P1.29_P1.29") (pintype "bidirectional"))
    )
    (net (code "75") (name "unconnected-(PB1-PadP1.31)") (class "Default")
      (node (ref "PB1") (pin "P1.31") (pinfunction "P1.31_P1.31") (pintype "bidirectional"))
    )
    (net (code "76") (name "unconnected-(PB1-PadP1.33)") (class "Default")
      (node (ref "PB1") (pin "P1.33") (pinfunction "P1.33_P1.33") (pintype "bidirectional"))
    )
    (net (code "77") (name "unconnected-(PB1-PadP1.34)") (class "Default")
      (node (ref "PB1") (pin "P1.34") (pinfunction "P1.34_P1.34") (pintype "bidirectional"))
    )
    (net (code "78") (name "unconnected-(PB1-PadP1.35)") (class "Default")
      (node (ref "PB1") (pin "P1.35") (pinfunction "P1.35_P1.35") (pintype "bidirectional"))
    )
    (net (code "79") (name "unconnected-(PB1-PadP1.36)") (class "Default")
      (node (ref "PB1") (pin "P1.36") (pinfunction "P1.36_P1.36") (pintype "bidirectional"))
    )
    (net (code "80") (name "unconnected-(PB1-PadP2.1)") (class "Default")
      (node (ref "PB1") (pin "P2.1") (pinfunction "P2.1_P2.1") (pintype "bidirectional"))
    )
    (net (code "81") (name "unconnected-(PB1-PadP2.2)") (class "Default")
      (node (ref "PB1") (pin "P2.2") (pinfunction "P2.2_P2.2") (pintype "bidirectional"))
    )
    (net (code "82") (name "unconnected-(PB1-PadP2.3)") (class "Default")
      (node (ref "PB1") (pin "P2.3") (pinfunction "P2.3_P2.3") (pintype "bidirectional"))
    )
    (net (code "83") (name "unconnected-(PB1-PadP2.4)") (class "Default")
      (node (ref "PB1") (pin "P2.4") (pinfunction "P2.4_P2.4") (pintype "bidirectional"))
    )
    (net (code "84") (name "unconnected-(PB1-PadP2.5)") (class "Default")
      (node (ref "PB1") (pin "P2.5") (pinfunction "P2.5_P2.5") (pintype "bidirectional"))
    )
    (net (code "85") (name "unconnected-(PB1-PadP2.6)") (class "Default")
      (node (ref "PB1") (pin "P2.6") (pinfunction "P2.6_P2.6") (pintype "bidirectional"))
    )
    (net (code "86") (name "unconnected-(PB1-PadP2.7)") (class "Default")
      (node (ref "PB1") (pin "P2.7") (pinfunction "P2.7_P2.7") (pintype "bidirectional"))
    )
    (net (code "87") (name "unconnected-(PB1-PadP2.8)") (class "Default")
      (node (ref "PB1") (pin "P2.8") (pinfunction "P2.8_P2.8") (pintype "bidirectional"))
    )
    (net (code "88") (name "unconnected-(PB1-PadP2.9)") (class "Default")
      (node (ref "PB1") (pin "P2.9") (pinfunction "P2.9_P2.9") (pintype "bidirectional"))
    )
    (net (code "89") (name "unconnected-(PB1-PadP2.10)") (class "Default")
      (node (ref "PB1") (pin "P2.10") (pinfunction "P2.10_P2.10") (pintype "bidirectional"))
    )
    (net (code "90") (name "unconnected-(PB1-PadP2.11)") (class "Default")
      (node (ref "PB1") (pin "P2.11") (pinfunction "P2.11_P2.11") (pintype "bidirectional"))
    )
    (net (code "91") (name "unconnected-(PB1-PadP2.12)") (class "Default")
      (node (ref "PB1") (pin "P2.12") (pinfunction "P2.12_P2.12") (pintype "bidirectional"))
    )
    (net (code "92") (name "unconnected-(PB1-PadP2.13)") (class "Default")
      (node (ref "PB1") (pin "P2.13") (pinfunction "P2.13_P2.13") (pintype "bidirectional"))
    )
    (net (code "93") (name "unconnected-(PB1-PadP2.14)") (class "Default")
      (node (ref "PB1") (pin "P2.14") (pinfunction "P2.14_P2.14") (pintype "bidirectional"))
    )
    (net (code "94") (name "unconnected-(PB1-PadP2.16)") (class "Default")
      (node (ref "PB1") (pin "P2.16") (pinfunction "P2.16_P2.16") (pintype "bidirectional"))
    )
    (net (code "95") (name "unconnected-(PB1-PadP2.17)") (class "Default")
      (node (ref "PB1") (pin "P2.17") (pinfunction "P2.17_P2.17") (pintype "bidirectional"))
    )
    (net (code "96") (name "unconnected-(PB1-PadP2.18)") (class "Default")
      (node (ref "PB1") (pin "P2.18") (pinfunction "P2.18_P2.18") (pintype "bidirectional"))
    )
    (net (code "97") (name "unconnected-(PB1-PadP2.19)") (class "Default")
      (node (ref "PB1") (pin "P2.19") (pinfunction "P2.19_P2.19") (pintype "bidirectional"))
    )
    (net (code "98") (name "unconnected-(PB1-PadP2.20)") (class "Default")
      (node (ref "PB1") (pin "P2.20") (pinfunction "P2.20_P2.20") (pintype "bidirectional"))
    )
    (net (code "99") (name "unconnected-(PB1-PadP2.22)") (class "Default")
      (node (ref "PB1") (pin "P2.22") (pinfunction "P2.22_P2.22") (pintype "bidirectional"))
    )
    (net (code "100") (name "unconnected-(PB1-PadP2.23)") (class "Default")
      (node (ref "PB1") (pin "P2.23") (pinfunction "P2.23_P2.23") (pintype "bidirectional"))
    )
    (net (code "101") (name "unconnected-(PB1-PadP2.24)") (class "Default")
      (node (ref "PB1") (pin "P2.24") (pinfunction "P2.24_P2.24") (pintype "bidirectional"))
    )
    (net (code "102") (name "unconnected-(PB1-PadP2.25)") (class "Default")
      (node (ref "PB1") (pin "P2.25") (pinfunction "P2.25_P2.25") (pintype "bidirectional"))
    )
    (net (code "103") (name "unconnected-(PB1-PadP2.26)") (class "Default")
      (node (ref "PB1") (pin "P2.26") (pinfunction "P2.26_P2.26") (pintype "bidirectional"))
    )
    (net (code "104") (name "unconnected-(PB1-PadP2.27)") (class "Default")
      (node (ref "PB1") (pin "P2.27") (pinfunction "P2.27_P2.27") (pintype "bidirectional"))
    )
    (net (code "105") (name "unconnected-(PB1-PadP2.28)") (class "Default")
      (node (ref "PB1") (pin "P2.28") (pinfunction "P2.28_P2.28") (pintype "bidirectional"))
    )
    (net (code "106") (name "unconnected-(PB1-PadP2.29)") (class "Default")
      (node (ref "PB1") (pin "P2.29") (pinfunction "P2.29_P2.29") (pintype "bidirectional"))
    )
    (net (code "107") (name "unconnected-(PB1-PadP2.30)") (class "Default")
      (node (ref "PB1") (pin "P2.30") (pinfunction "P2.30_P2.30") (pintype "bidirectional"))
    )
    (net (code "108") (name "unconnected-(PB1-PadP2.31)") (class "Default")
      (node (ref "PB1") (pin "P2.31") (pinfunction "P2.31_P2.31") (pintype "bidirectional"))
    )
    (net (code "109") (name "unconnected-(PB1-PadP2.32)") (class "Default")
      (node (ref "PB1") (pin "P2.32") (pinfunction "P2.32_P2.32") (pintype "bidirectional"))
    )
    (net (code "110") (name "unconnected-(PB1-PadP2.33)") (class "Default")
      (node (ref "PB1") (pin "P2.33") (pinfunction "P2.33_P2.33") (pintype "bidirectional"))
    )
    (net (code "111") (name "unconnected-(PB1-PadP2.34)") (class "Default")
      (node (ref "PB1") (pin "P2.34") (pinfunction "P2.34_P2.34") (pintype "bidirectional"))
    )
    (net (code "112") (name "unconnected-(PB1-PadP2.35)") (class "Default")
      (node (ref "PB1") (pin "P2.35") (pinfunction "P2.35_P2.35") (pintype "bidirectional"))
    )
    (net (code "113") (name "unconnected-(PB1-PadP2.36)") (class "Default")
      (node (ref "PB1") (pin "P2.36") (pinfunction "P2.36_P2.36") (pintype "bidirectional"))
    )
    (net (code "114") (name "~{FDX_LED}") (class "Default")
      (node (ref "D1") (pin "P$2") (pinfunction "K_P$2") (pintype "passive"))
      (node (ref "IC1") (pin "26") (pinfunction "GPIO8_26") (pintype "bidirectional"))
    )
    (net (code "115") (name "~{LNKA_LED}") (class "Default")
      (node (ref "IC1") (pin "27") (pinfunction "GPIO9_27") (pintype "bidirectional"))
      (node (ref "R6") (pin "1") (pinfunction "1_1") (pintype "passive"))
    )
    (net (code "116") (name "~{SPD_LED}") (class "Default")
      (node (ref "IC1") (pin "28") (pinfunction "GPIO10_28") (pintype "bidirectional"))
      (node (ref "R5") (pin "1") (pinfunction "1_1") (pintype "passive"))
    )
  )
)
